# Industrial-Controller_MCU1.net
KiCad netlist of a schematic drawn in Altium Designer
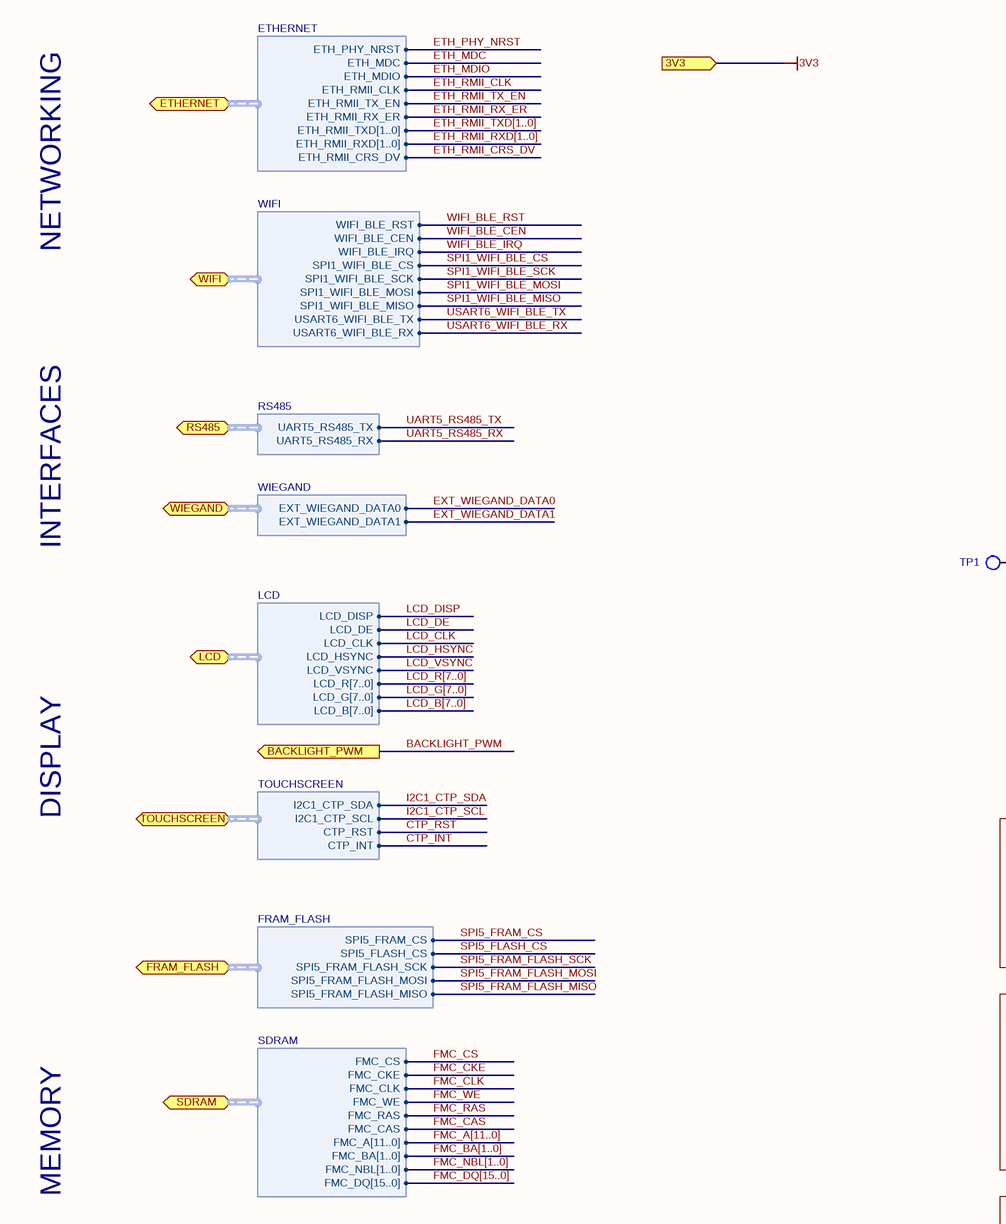
[diagram p0: Industrial-Controller_MCU1.SchDoc, top left]
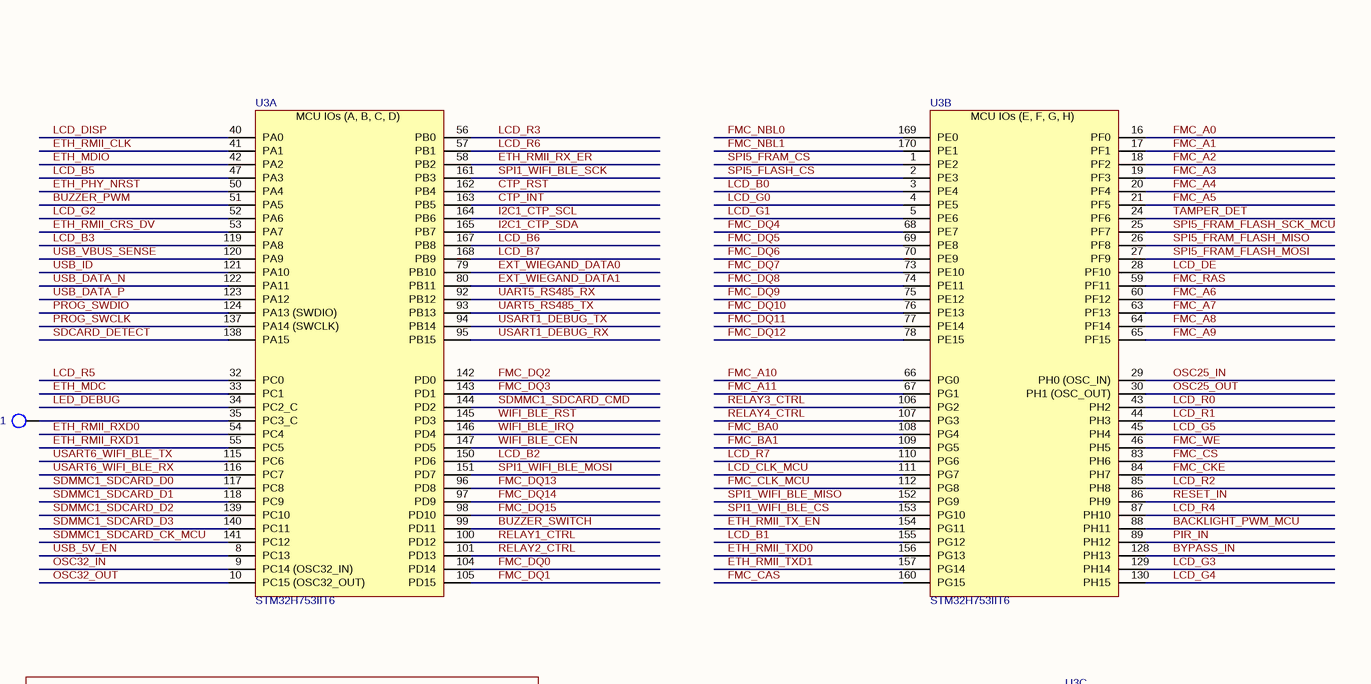
[diagram p1: Industrial-Controller_MCU1.SchDoc, top right]
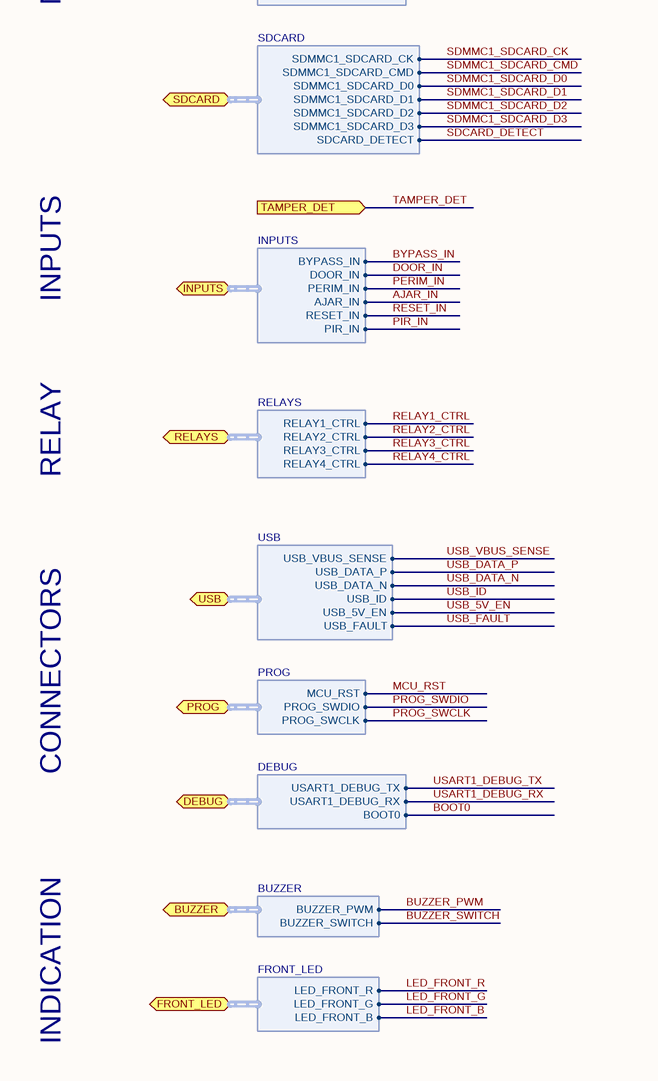
[diagram p2: Industrial-Controller_MCU1.SchDoc, bottom left]
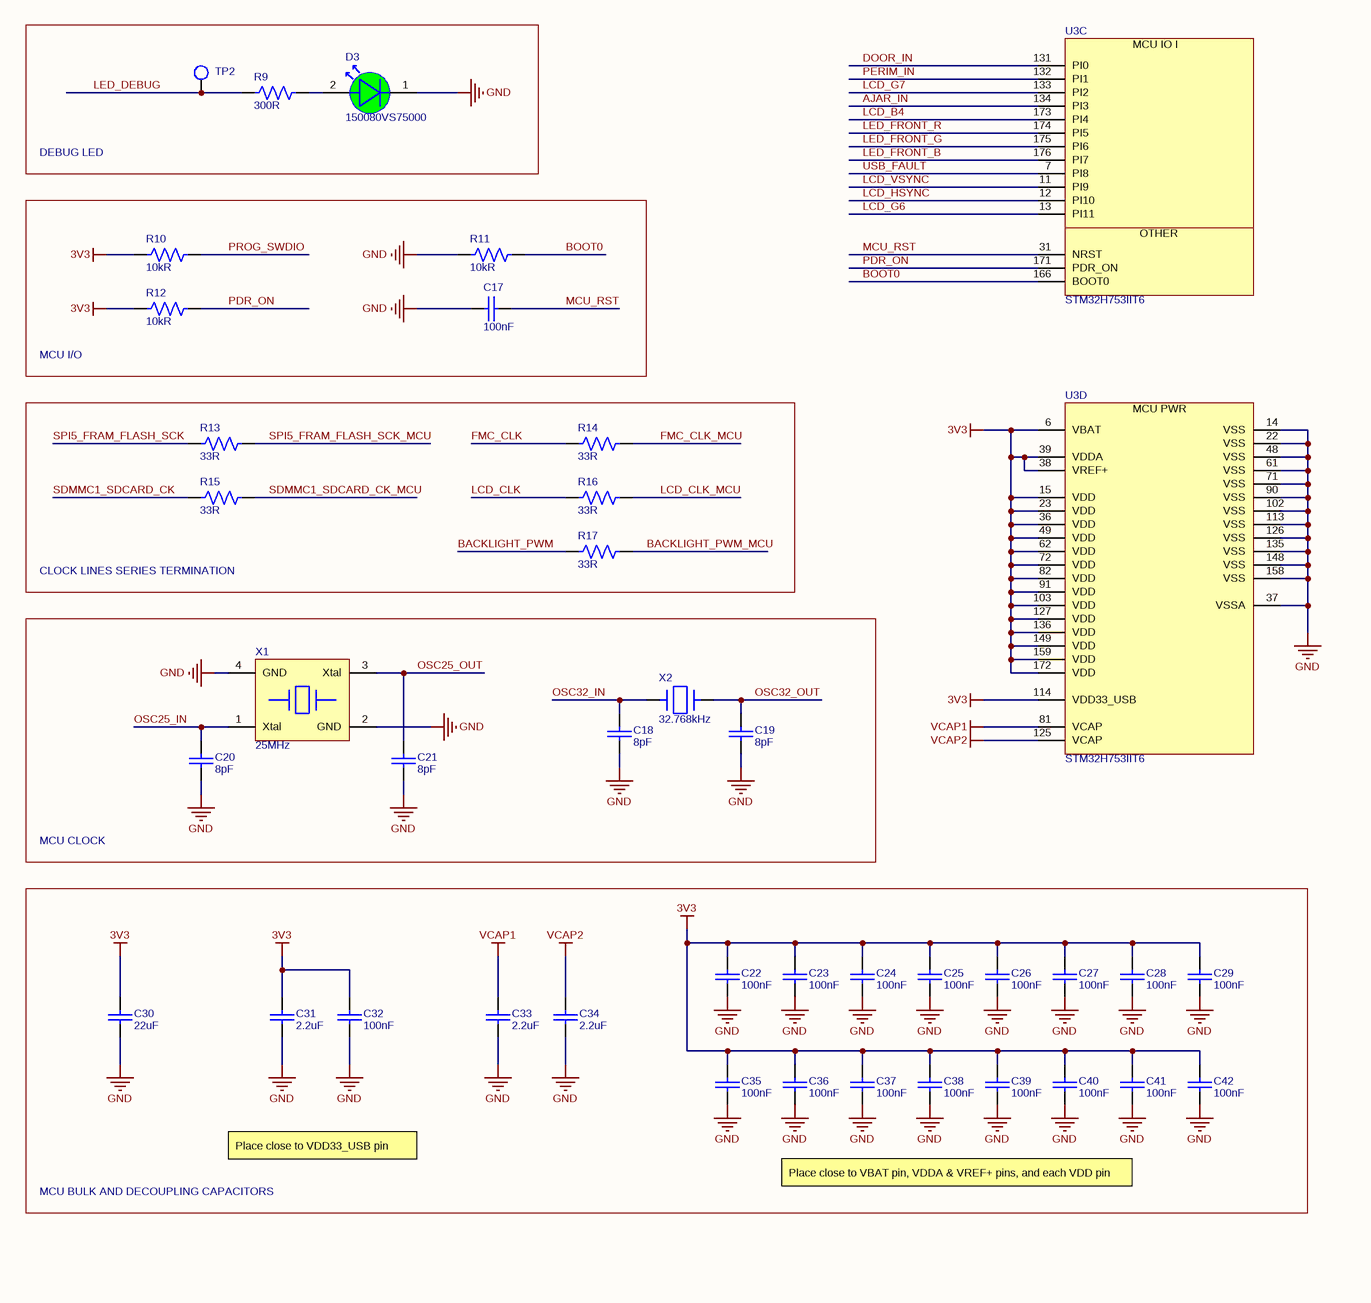
[diagram p3: Industrial-Controller_MCU1.SchDoc, bottom right]

(export (version "E")
  (design (tool "Eeschema 10.0.6"))
  (components
    (comp (ref "C17")
      (value "100nF")
      (footprint "CAP_0603")
      (description "CAP CER 0.1UF 50V X7R 0603")
      (fields (field (name "TOLERANCE") "10%"))
      (libsource (lib "Door_Controller_Single") (part "CL10B104KB8NNNL"))
    )
    (comp (ref "C18")
      (value "8pF")
      (footprint "CAP_0603")
      (description "CAP CER 8PF 50V C0G/NPO 0603")
      (libsource (lib "Door_Controller_Single") (part "CC0603DRNPO9BN8R0"))
    )
    (comp (ref "C19")
      (value "8pF")
      (footprint "CAP_0603")
      (description "CAP CER 8PF 50V C0G/NPO 0603")
      (libsource (lib "Door_Controller_Single") (part "CC0603DRNPO9BN8R0"))
    )
    (comp (ref "C20")
      (value "8pF")
      (footprint "CAP_0603")
      (description "CAP CER 8PF 50V C0G/NPO 0603")
      (libsource (lib "Door_Controller_Single") (part "CC0603DRNPO9BN8R0"))
    )
    (comp (ref "C21")
      (value "8pF")
      (footprint "CAP_0603")
      (description "CAP CER 8PF 50V C0G/NPO 0603")
      (libsource (lib "Door_Controller_Single") (part "CC0603DRNPO9BN8R0"))
    )
    (comp (ref "C22")
      (value "100nF")
      (footprint "CAP_0603")
      (description "CAP CER 0.1UF 50V X7R 0603")
      (fields (field (name "TOLERANCE") "10%"))
      (libsource (lib "Door_Controller_Single") (part "CL10B104KB8NNNL"))
    )
    (comp (ref "C23")
      (value "100nF")
      (footprint "CAP_0603")
      (description "CAP CER 0.1UF 50V X7R 0603")
      (fields (field (name "TOLERANCE") "10%"))
      (libsource (lib "Door_Controller_Single") (part "CL10B104KB8NNNL"))
    )
    (comp (ref "C24")
      (value "100nF")
      (footprint "CAP_0603")
      (description "CAP CER 0.1UF 50V X7R 0603")
      (fields (field (name "TOLERANCE") "10%"))
      (libsource (lib "Door_Controller_Single") (part "CL10B104KB8NNNL"))
    )
    (comp (ref "C25")
      (value "100nF")
      (footprint "CAP_0603")
      (description "CAP CER 0.1UF 50V X7R 0603")
      (fields (field (name "TOLERANCE") "10%"))
      (libsource (lib "Door_Controller_Single") (part "CL10B104KB8NNNL"))
    )
    (comp (ref "C26")
      (value "100nF")
      (footprint "CAP_0603")
      (description "CAP CER 0.1UF 50V X7R 0603")
      (fields (field (name "TOLERANCE") "10%"))
      (libsource (lib "Door_Controller_Single") (part "CL10B104KB8NNNL"))
    )
    (comp (ref "C27")
      (value "100nF")
      (footprint "CAP_0603")
      (description "CAP CER 0.1UF 50V X7R 0603")
      (fields (field (name "TOLERANCE") "10%"))
      (libsource (lib "Door_Controller_Single") (part "CL10B104KB8NNNL"))
    )
    (comp (ref "C28")
      (value "100nF")
      (footprint "CAP_0603")
      (description "CAP CER 0.1UF 50V X7R 0603")
      (fields (field (name "TOLERANCE") "10%"))
      (libsource (lib "Door_Controller_Single") (part "CL10B104KB8NNNL"))
    )
    (comp (ref "C29")
      (value "100nF")
      (footprint "CAP_0603")
      (description "CAP CER 0.1UF 50V X7R 0603")
      (fields (field (name "TOLERANCE") "10%"))
      (libsource (lib "Door_Controller_Single") (part "CL10B104KB8NNNL"))
    )
    (comp (ref "C30")
      (value "22uF")
      (footprint "CAP_1210")
      (description "CAP CER 22UF 25V X7R 1210")
      (fields (field (name "TOLERANCE") "10%"))
      (libsource (lib "Door_Controller_Single") (part "CL32B226KAJNNNE"))
    )
    (comp (ref "C31")
      (value "2.2uF")
      (footprint "CAP_0603")
      (description "CAP CER 2.2UF 10V X7R 0603")
      (fields (field (name "TOLERANCE") "10%"))
      (libsource (lib "Door_Controller_Single") (part "CL10B225KP8NNNC"))
    )
    (comp (ref "C32")
      (value "100nF")
      (footprint "CAP_0603")
      (description "CAP CER 0.1UF 50V X7R 0603")
      (fields (field (name "TOLERANCE") "10%"))
      (libsource (lib "Door_Controller_Single") (part "CL10B104KB8NNNL"))
    )
    (comp (ref "C33")
      (value "2.2uF")
      (footprint "CAP_0603")
      (description "CAP CER 2.2UF 10V X7R 0603")
      (fields (field (name "TOLERANCE") "10%"))
      (libsource (lib "Door_Controller_Single") (part "CL10B225KP8NNNC"))
    )
    (comp (ref "C34")
      (value "2.2uF")
      (footprint "CAP_0603")
      (description "CAP CER 2.2UF 10V X7R 0603")
      (fields (field (name "TOLERANCE") "10%"))
      (libsource (lib "Door_Controller_Single") (part "CL10B225KP8NNNC"))
    )
    (comp (ref "C35")
      (value "100nF")
      (footprint "CAP_0603")
      (description "CAP CER 0.1UF 50V X7R 0603")
      (fields (field (name "TOLERANCE") "10%"))
      (libsource (lib "Door_Controller_Single") (part "CL10B104KB8NNNL"))
    )
    (comp (ref "C36")
      (value "100nF")
      (footprint "CAP_0603")
      (description "CAP CER 0.1UF 50V X7R 0603")
      (fields (field (name "TOLERANCE") "10%"))
      (libsource (lib "Door_Controller_Single") (part "CL10B104KB8NNNL"))
    )
    (comp (ref "C37")
      (value "100nF")
      (footprint "CAP_0603")
      (description "CAP CER 0.1UF 50V X7R 0603")
      (fields (field (name "TOLERANCE") "10%"))
      (libsource (lib "Door_Controller_Single") (part "CL10B104KB8NNNL"))
    )
    (comp (ref "C38")
      (value "100nF")
      (footprint "CAP_0603")
      (description "CAP CER 0.1UF 50V X7R 0603")
      (fields (field (name "TOLERANCE") "10%"))
      (libsource (lib "Door_Controller_Single") (part "CL10B104KB8NNNL"))
    )
    (comp (ref "C39")
      (value "100nF")
      (footprint "CAP_0603")
      (description "CAP CER 0.1UF 50V X7R 0603")
      (fields (field (name "TOLERANCE") "10%"))
      (libsource (lib "Door_Controller_Single") (part "CL10B104KB8NNNL"))
    )
    (comp (ref "C40")
      (value "100nF")
      (footprint "CAP_0603")
      (description "CAP CER 0.1UF 50V X7R 0603")
      (fields (field (name "TOLERANCE") "10%"))
      (libsource (lib "Door_Controller_Single") (part "CL10B104KB8NNNL"))
    )
    (comp (ref "C41")
      (value "100nF")
      (footprint "CAP_0603")
      (description "CAP CER 0.1UF 50V X7R 0603")
      (fields (field (name "TOLERANCE") "10%"))
      (libsource (lib "Door_Controller_Single") (part "CL10B104KB8NNNL"))
    )
    (comp (ref "C42")
      (value "100nF")
      (footprint "CAP_0603")
      (description "CAP CER 0.1UF 50V X7R 0603")
      (fields (field (name "TOLERANCE") "10%"))
      (libsource (lib "Door_Controller_Single") (part "CL10B104KB8NNNL"))
    )
    (comp (ref "D3")
      (value "150080VS75000")
      (footprint "LED_0805")
      (description "LED GREEN CLEAR 0805 SMD")
      (libsource (lib "Door_Controller_Single") (part "150080VS75000"))
    )
    (comp (ref "R9")
      (value "300R")
      (footprint "RES_0603")
      (description "RES 300 OHM 5% 1/10W 0603")
      (fields (field (name "TOLERANCE") "5%"))
      (libsource (lib "Door_Controller_Single") (part "RC0603JR-07300RL"))
    )
    (comp (ref "R10")
      (value "10kR")
      (footprint "RES_0603")
      (description "RES SMD 10K OHM 5% 1/10W 0603")
      (fields (field (name "TOLERANCE") "5%"))
      (libsource (lib "Door_Controller_Single") (part "RC0603JR-0710KP"))
    )
    (comp (ref "R11")
      (value "10kR")
      (footprint "RES_0603")
      (description "RES SMD 10K OHM 5% 1/10W 0603")
      (fields (field (name "TOLERANCE") "5%"))
      (libsource (lib "Door_Controller_Single") (part "RC0603JR-0710KP"))
    )
    (comp (ref "R12")
      (value "10kR")
      (footprint "RES_0603")
      (description "RES SMD 10K OHM 5% 1/10W 0603")
      (fields (field (name "TOLERANCE") "5%"))
      (libsource (lib "Door_Controller_Single") (part "RC0603JR-0710KP"))
    )
    (comp (ref "R13")
      (value "33R")
      (footprint "RES_0603")
      (description "RES 33 OHM 5% 1/10W 0603")
      (fields (field (name "TOLERANCE") "5%"))
      (libsource (lib "Door_Controller_Single") (part "RC0603JR-0733RL"))
    )
    (comp (ref "R14")
      (value "33R")
      (footprint "RES_0603")
      (description "RES 33 OHM 5% 1/10W 0603")
      (fields (field (name "TOLERANCE") "5%"))
      (libsource (lib "Door_Controller_Single") (part "RC0603JR-0733RL"))
    )
    (comp (ref "R15")
      (value "33R")
      (footprint "RES_0603")
      (description "RES 33 OHM 5% 1/10W 0603")
      (fields (field (name "TOLERANCE") "5%"))
      (libsource (lib "Door_Controller_Single") (part "RC0603JR-0733RL"))
    )
    (comp (ref "R16")
      (value "33R")
      (footprint "RES_0603")
      (description "RES 33 OHM 5% 1/10W 0603")
      (fields (field (name "TOLERANCE") "5%"))
      (libsource (lib "Door_Controller_Single") (part "RC0603JR-0733RL"))
    )
    (comp (ref "R17")
      (value "33R")
      (footprint "RES_0603")
      (description "RES 33 OHM 5% 1/10W 0603")
      (fields (field (name "TOLERANCE") "5%"))
      (libsource (lib "Door_Controller_Single") (part "RC0603JR-0733RL"))
    )
    (comp (ref "TP1")
      (value "TEST_POINT_SMT")
      (footprint "TEST_POINT_SMT")
      (description "STM test point")
      (libsource (lib "Door_Controller_Single") (part "TEST_POINT_SMT"))
    )
    (comp (ref "TP2")
      (value "TEST_POINT_SMT")
      (footprint "TEST_POINT_SMT")
      (description "STM test point")
      (libsource (lib "Door_Controller_Single") (part "TEST_POINT_SMT"))
    )
    (comp (ref "U3")
      (value "STM32H753IIT6")
      (footprint "LQFP176")
      (description "IC MCU 32BIT 2MB FLASH 176LQFP")
      (libsource (lib "Door_Controller_Single") (part "STM32H753IIT6"))
    )
    (comp (ref "X1")
      (value "25MHz")
      (footprint "NX2016SA-25MHZ-EXS00A-CS11365")
      (description "Crystal 25.0000MHZ 6PF SMD")
      (libsource (lib "Door_Controller_Single") (part "NX2016SA-25MHZ-EXS00A-CS11365"))
    )
    (comp (ref "X2")
      (value "32.768kHz")
      (footprint "NX2012SA-32.768KHZ-EXS00A-MU00626")
      (description "Crystal 32.7680KHZ 6PF SMD")
      (libsource (lib "Door_Controller_Single") (part "NX2012SA-32.768KHZ-EXS00A-MU00626"))
    )
  )
  (nets
    (net (code "17") (name "/AJAR_IN") (class "Default")
      (node (ref "U3") (pin "134") (pinfunction "PI3_134") (pintype "passive"))
    )
    (net (code "18") (name "/BACKLIGHT_PWM") (class "Default")
      (node (ref "R17") (pin "1") (pinfunction "1_1") (pintype "passive"))
    )
    (net (code "19") (name "/BACKLIGHT_PWM_MCU") (class "Default")
      (node (ref "R17") (pin "2") (pinfunction "2_2") (pintype "passive"))
      (node (ref "U3") (pin "88") (pinfunction "PH11_88") (pintype "passive"))
    )
    (net (code "20") (name "/BOOT0") (class "Default")
      (node (ref "R11") (pin "2") (pinfunction "2_2") (pintype "passive"))
      (node (ref "U3") (pin "166") (pinfunction "BOOT0_166") (pintype "passive"))
    )
    (net (code "21") (name "/BUZZER_PWM") (class "Default")
      (node (ref "U3") (pin "51") (pinfunction "PA5_51") (pintype "passive"))
    )
    (net (code "22") (name "/BUZZER_SWITCH") (class "Default")
      (node (ref "U3") (pin "99") (pinfunction "PD11_99") (pintype "passive"))
    )
    (net (code "23") (name "/BYPASS_IN") (class "Default")
      (node (ref "U3") (pin "128") (pinfunction "PH13_128") (pintype "passive"))
    )
    (net (code "24") (name "/CTP_INT") (class "Default")
      (node (ref "U3") (pin "163") (pinfunction "PB5_163") (pintype "passive"))
    )
    (net (code "25") (name "/CTP_RST") (class "Default")
      (node (ref "U3") (pin "162") (pinfunction "PB4_162") (pintype "passive"))
    )
    (net (code "26") (name "/DOOR_IN") (class "Default")
      (node (ref "U3") (pin "131") (pinfunction "PI0_131") (pintype "passive"))
    )
    (net (code "28") (name "/ETH_MDC") (class "Default")
      (node (ref "U3") (pin "33") (pinfunction "PC1_33") (pintype "passive"))
    )
    (net (code "29") (name "/ETH_MDIO") (class "Default")
      (node (ref "U3") (pin "42") (pinfunction "PA2_42") (pintype "passive"))
    )
    (net (code "30") (name "/ETH_PHY_NRST") (class "Default")
      (node (ref "U3") (pin "50") (pinfunction "PA4_50") (pintype "passive"))
    )
    (net (code "31") (name "/ETH_RMII_CLK") (class "Default")
      (node (ref "U3") (pin "41") (pinfunction "PA1_41") (pintype "passive"))
    )
    (net (code "32") (name "/ETH_RMII_CRS_DV") (class "Default")
      (node (ref "U3") (pin "53") (pinfunction "PA7_53") (pintype "passive"))
    )
    (net (code "33") (name "/ETH_RMII_RXD0") (class "Default")
      (node (ref "U3") (pin "54") (pinfunction "PC4_54") (pintype "passive"))
    )
    (net (code "34") (name "/ETH_RMII_RXD1") (class "Default")
      (node (ref "U3") (pin "55") (pinfunction "PC5_55") (pintype "passive"))
    )
    (net (code "35") (name "/ETH_RMII_RX_ER") (class "Default")
      (node (ref "U3") (pin "58") (pinfunction "PB2_58") (pintype "passive"))
    )
    (net (code "36") (name "/ETH_RMII_TXD0") (class "Default")
      (node (ref "U3") (pin "156") (pinfunction "PG13_156") (pintype "passive"))
    )
    (net (code "37") (name "/ETH_RMII_TXD1") (class "Default")
      (node (ref "U3") (pin "157") (pinfunction "PG14_157") (pintype "passive"))
    )
    (net (code "39") (name "/ETH_RMII_TX_EN") (class "Default")
      (node (ref "U3") (pin "154") (pinfunction "PG11_154") (pintype "passive"))
    )
    (net (code "40") (name "/EXT_WIEGAND_DATA0") (class "Default")
      (node (ref "U3") (pin "79") (pinfunction "PB10_79") (pintype "passive"))
    )
    (net (code "41") (name "/EXT_WIEGAND_DATA1") (class "Default")
      (node (ref "U3") (pin "80") (pinfunction "PB11_80") (pintype "passive"))
    )
    (net (code "42") (name "/FMC_A0") (class "Default")
      (node (ref "U3") (pin "16") (pinfunction "PF0_16") (pintype "passive"))
    )
    (net (code "43") (name "/FMC_A1") (class "Default")
      (node (ref "U3") (pin "17") (pinfunction "PF1_17") (pintype "passive"))
    )
    (net (code "44") (name "/FMC_A2") (class "Default")
      (node (ref "U3") (pin "18") (pinfunction "PF2_18") (pintype "passive"))
    )
    (net (code "45") (name "/FMC_A3") (class "Default")
      (node (ref "U3") (pin "19") (pinfunction "PF3_19") (pintype "passive"))
    )
    (net (code "46") (name "/FMC_A4") (class "Default")
      (node (ref "U3") (pin "20") (pinfunction "PF4_20") (pintype "passive"))
    )
    (net (code "47") (name "/FMC_A5") (class "Default")
      (node (ref "U3") (pin "21") (pinfunction "PF5_21") (pintype "passive"))
    )
    (net (code "48") (name "/FMC_A6") (class "Default")
      (node (ref "U3") (pin "60") (pinfunction "PF12_60") (pintype "passive"))
    )
    (net (code "49") (name "/FMC_A7") (class "Default")
      (node (ref "U3") (pin "63") (pinfunction "PF13_63") (pintype "passive"))
    )
    (net (code "50") (name "/FMC_A8") (class "Default")
      (node (ref "U3") (pin "64") (pinfunction "PF14_64") (pintype "passive"))
    )
    (net (code "51") (name "/FMC_A9") (class "Default")
      (node (ref "U3") (pin "65") (pinfunction "PF15_65") (pintype "passive"))
    )
    (net (code "52") (name "/FMC_A10") (class "Default")
      (node (ref "U3") (pin "66") (pinfunction "PG0_66") (pintype "passive"))
    )
    (net (code "53") (name "/FMC_A11") (class "Default")
      (node (ref "U3") (pin "67") (pinfunction "PG1_67") (pintype "passive"))
    )
    (net (code "54") (name "/FMC_BA0") (class "Default")
      (node (ref "U3") (pin "108") (pinfunction "PG4_108") (pintype "passive"))
    )
    (net (code "55") (name "/FMC_BA1") (class "Default")
      (node (ref "U3") (pin "109") (pinfunction "PG5_109") (pintype "passive"))
    )
    (net (code "57") (name "/FMC_CAS") (class "Default")
      (node (ref "U3") (pin "160") (pinfunction "PG15_160") (pintype "passive"))
    )
    (net (code "58") (name "/FMC_CKE") (class "Default")
      (node (ref "U3") (pin "84") (pinfunction "PH7_84") (pintype "passive"))
    )
    (net (code "59") (name "/FMC_CLK") (class "Default")
      (node (ref "R14") (pin "1") (pinfunction "1_1") (pintype "passive"))
    )
    (net (code "60") (name "/FMC_CLK_MCU") (class "Default")
      (node (ref "R14") (pin "2") (pinfunction "2_2") (pintype "passive"))
      (node (ref "U3") (pin "112") (pinfunction "PG8_112") (pintype "passive"))
    )
    (net (code "61") (name "/FMC_CS") (class "Default")
      (node (ref "U3") (pin "83") (pinfunction "PH6_83") (pintype "passive"))
    )
    (net (code "62") (name "/FMC_DQ0") (class "Default")
      (node (ref "U3") (pin "104") (pinfunction "PD14_104") (pintype "passive"))
    )
    (net (code "63") (name "/FMC_DQ1") (class "Default")
      (node (ref "U3") (pin "105") (pinfunction "PD15_105") (pintype "passive"))
    )
    (net (code "64") (name "/FMC_DQ2") (class "Default")
      (node (ref "U3") (pin "142") (pinfunction "PD0_142") (pintype "passive"))
    )
    (net (code "65") (name "/FMC_DQ3") (class "Default")
      (node (ref "U3") (pin "143") (pinfunction "PD1_143") (pintype "passive"))
    )
    (net (code "66") (name "/FMC_DQ4") (class "Default")
      (node (ref "U3") (pin "68") (pinfunction "PE7_68") (pintype "passive"))
    )
    (net (code "67") (name "/FMC_DQ5") (class "Default")
      (node (ref "U3") (pin "69") (pinfunction "PE8_69") (pintype "passive"))
    )
    (net (code "68") (name "/FMC_DQ6") (class "Default")
      (node (ref "U3") (pin "70") (pinfunction "PE9_70") (pintype "passive"))
    )
    (net (code "69") (name "/FMC_DQ7") (class "Default")
      (node (ref "U3") (pin "73") (pinfunction "PE10_73") (pintype "passive"))
    )
    (net (code "70") (name "/FMC_DQ8") (class "Default")
      (node (ref "U3") (pin "74") (pinfunction "PE11_74") (pintype "passive"))
    )
    (net (code "71") (name "/FMC_DQ9") (class "Default")
      (node (ref "U3") (pin "75") (pinfunction "PE12_75") (pintype "passive"))
    )
    (net (code "72") (name "/FMC_DQ10") (class "Default")
      (node (ref "U3") (pin "76") (pinfunction "PE13_76") (pintype "passive"))
    )
    (net (code "73") (name "/FMC_DQ11") (class "Default")
      (node (ref "U3") (pin "77") (pinfunction "PE14_77") (pintype "passive"))
    )
    (net (code "74") (name "/FMC_DQ12") (class "Default")
      (node (ref "U3") (pin "78") (pinfunction "PE15_78") (pintype "passive"))
    )
    (net (code "75") (name "/FMC_DQ13") (class "Default")
      (node (ref "U3") (pin "96") (pinfunction "PD8_96") (pintype "passive"))
    )
    (net (code "76") (name "/FMC_DQ14") (class "Default")
      (node (ref "U3") (pin "97") (pinfunction "PD9_97") (pintype "passive"))
    )
    (net (code "77") (name "/FMC_DQ15") (class "Default")
      (node (ref "U3") (pin "98") (pinfunction "PD10_98") (pintype "passive"))
    )
    (net (code "79") (name "/FMC_NBL0") (class "Default")
      (node (ref "U3") (pin "169") (pinfunction "PE0_169") (pintype "passive"))
    )
    (net (code "80") (name "/FMC_NBL1") (class "Default")
      (node (ref "U3") (pin "170") (pinfunction "PE1_170") (pintype "passive"))
    )
    (net (code "82") (name "/FMC_RAS") (class "Default")
      (node (ref "U3") (pin "59") (pinfunction "PF11_59") (pintype "passive"))
    )
    (net (code "83") (name "/FMC_WE") (class "Default")
      (node (ref "U3") (pin "46") (pinfunction "PH5_46") (pintype "passive"))
    )
    (net (code "84") (name "/I2C1_CTP_SCL") (class "Default")
      (node (ref "U3") (pin "164") (pinfunction "PB6_164") (pintype "passive"))
    )
    (net (code "85") (name "/I2C1_CTP_SDA") (class "Default")
      (node (ref "U3") (pin "165") (pinfunction "PB7_165") (pintype "passive"))
    )
    (net (code "86") (name "/LCD_B0") (class "Default")
      (node (ref "U3") (pin "3") (pinfunction "PE4_3") (pintype "passive"))
    )
    (net (code "87") (name "/LCD_B1") (class "Default")
      (node (ref "U3") (pin "155") (pinfunction "PG12_155") (pintype "passive"))
    )
    (net (code "88") (name "/LCD_B2") (class "Default")
      (node (ref "U3") (pin "150") (pinfunction "PD6_150") (pintype "passive"))
    )
    (net (code "89") (name "/LCD_B3") (class "Default")
      (node (ref "U3") (pin "119") (pinfunction "PA8_119") (pintype "passive"))
    )
    (net (code "90") (name "/LCD_B4") (class "Default")
      (node (ref "U3") (pin "173") (pinfunction "PI4_173") (pintype "passive"))
    )
    (net (code "91") (name "/LCD_B5") (class "Default")
      (node (ref "U3") (pin "47") (pinfunction "PA3_47") (pintype "passive"))
    )
    (net (code "92") (name "/LCD_B6") (class "Default")
      (node (ref "U3") (pin "167") (pinfunction "PB8_167") (pintype "passive"))
    )
    (net (code "93") (name "/LCD_B7") (class "Default")
      (node (ref "U3") (pin "168") (pinfunction "PB9_168") (pintype "passive"))
    )
    (net (code "94") (name "/LCD_CLK") (class "Default")
      (node (ref "R16") (pin "1") (pinfunction "1_1") (pintype "passive"))
    )
    (net (code "95") (name "/LCD_CLK_MCU") (class "Default")
      (node (ref "R16") (pin "2") (pinfunction "2_2") (pintype "passive"))
      (node (ref "U3") (pin "111") (pinfunction "PG7_111") (pintype "passive"))
    )
    (net (code "96") (name "/LCD_DE") (class "Default")
      (node (ref "U3") (pin "28") (pinfunction "PF10_28") (pintype "passive"))
    )
    (net (code "97") (name "/LCD_DISP") (class "Default")
      (node (ref "U3") (pin "40") (pinfunction "PA0_40") (pintype "passive"))
    )
    (net (code "98") (name "/LCD_G0") (class "Default")
      (node (ref "U3") (pin "4") (pinfunction "PE5_4") (pintype "passive"))
    )
    (net (code "99") (name "/LCD_G1") (class "Default")
      (node (ref "U3") (pin "5") (pinfunction "PE6_5") (pintype "passive"))
    )
    (net (code "100") (name "/LCD_G2") (class "Default")
      (node (ref "U3") (pin "52") (pinfunction "PA6_52") (pintype "passive"))
    )
    (net (code "101") (name "/LCD_G3") (class "Default")
      (node (ref "U3") (pin "129") (pinfunction "PH14_129") (pintype "passive"))
    )
    (net (code "102") (name "/LCD_G4") (class "Default")
      (node (ref "U3") (pin "130") (pinfunction "PH15_130") (pintype "passive"))
    )
    (net (code "103") (name "/LCD_G5") (class "Default")
      (node (ref "U3") (pin "45") (pinfunction "PH4_45") (pintype "passive"))
    )
    (net (code "104") (name "/LCD_G6") (class "Default")
      (node (ref "U3") (pin "13") (pinfunction "PI11_13") (pintype "passive"))
    )
    (net (code "105") (name "/LCD_G7") (class "Default")
      (node (ref "U3") (pin "133") (pinfunction "PI2_133") (pintype "passive"))
    )
    (net (code "107") (name "/LCD_HSYNC") (class "Default")
      (node (ref "U3") (pin "12") (pinfunction "PI10_12") (pintype "passive"))
    )
    (net (code "108") (name "/LCD_R0") (class "Default")
      (node (ref "U3") (pin "43") (pinfunction "PH2_43") (pintype "passive"))
    )
    (net (code "109") (name "/LCD_R1") (class "Default")
      (node (ref "U3") (pin "44") (pinfunction "PH3_44") (pintype "passive"))
    )
    (net (code "110") (name "/LCD_R2") (class "Default")
      (node (ref "U3") (pin "85") (pinfunction "PH8_85") (pintype "passive"))
    )
    (net (code "111") (name "/LCD_R3") (class "Default")
      (node (ref "U3") (pin "56") (pinfunction "PB0_56") (pintype "passive"))
    )
    (net (code "112") (name "/LCD_R4") (class "Default")
      (node (ref "U3") (pin "87") (pinfunction "PH10_87") (pintype "passive"))
    )
    (net (code "113") (name "/LCD_R5") (class "Default")
      (node (ref "U3") (pin "32") (pinfunction "PC0_32") (pintype "passive"))
    )
    (net (code "114") (name "/LCD_R6") (class "Default")
      (node (ref "U3") (pin "57") (pinfunction "PB1_57") (pintype "passive"))
    )
    (net (code "115") (name "/LCD_R7") (class "Default")
      (node (ref "U3") (pin "110") (pinfunction "PG6_110") (pintype "passive"))
    )
    (net (code "117") (name "/LCD_VSYNC") (class "Default")
      (node (ref "U3") (pin "11") (pinfunction "PI9_11") (pintype "passive"))
    )
    (net (code "119") (name "/LED_DEBUG") (class "Default")
      (node (ref "R9") (pin "1") (pinfunction "1_1") (pintype "passive"))
      (node (ref "TP2") (pin "1") (pinfunction "1_1") (pintype "passive"))
      (node (ref "U3") (pin "34") (pinfunction "PC2_C_34") (pintype "passive"))
    )
    (net (code "120") (name "/LED_FRONT_B") (class "Default")
      (node (ref "U3") (pin "176") (pinfunction "PI7_176") (pintype "passive"))
    )
    (net (code "121") (name "/LED_FRONT_G") (class "Default")
      (node (ref "U3") (pin "175") (pinfunction "PI6_175") (pintype "passive"))
    )
    (net (code "122") (name "/LED_FRONT_R") (class "Default")
      (node (ref "U3") (pin "174") (pinfunction "PI5_174") (pintype "passive"))
    )
    (net (code "123") (name "/MCU_RST") (class "Default")
      (node (ref "C17") (pin "2") (pinfunction "2_2") (pintype "passive"))
      (node (ref "U3") (pin "31") (pinfunction "NRST_31") (pintype "passive"))
    )
    (net (code "124") (name "/OSC25_IN") (class "Default")
      (node (ref "C20") (pin "2") (pinfunction "2_2") (pintype "passive"))
      (node (ref "U3") (pin "29") (pinfunction "PH0_(OSC_IN)_29") (pintype "passive"))
      (node (ref "X1") (pin "1") (pinfunction "Xtal_1") (pintype "passive"))
    )
    (net (code "125") (name "/OSC25_OUT") (class "Default")
      (node (ref "C21") (pin "2") (pinfunction "2_2") (pintype "passive"))
      (node (ref "U3") (pin "30") (pinfunction "PH1_(OSC_OUT)_30") (pintype "passive"))
      (node (ref "X1") (pin "3") (pinfunction "Xtal_3") (pintype "passive"))
    )
    (net (code "126") (name "/OSC32_IN") (class "Default")
      (node (ref "C18") (pin "2") (pinfunction "2_2") (pintype "passive"))
      (node (ref "U3") (pin "9") (pinfunction "PC14_(OSC32_IN)_9") (pintype "passive"))
      (node (ref "X2") (pin "1") (pinfunction "1_1") (pintype "passive"))
    )
    (net (code "127") (name "/OSC32_OUT") (class "Default")
      (node (ref "C19") (pin "2") (pinfunction "2_2") (pintype "passive"))
      (node (ref "U3") (pin "10") (pinfunction "PC15_(OSC32_OUT)_10") (pintype "passive"))
      (node (ref "X2") (pin "2") (pinfunction "2_2") (pintype "passive"))
    )
    (net (code "128") (name "/PDR_ON") (class "Default")
      (node (ref "R12") (pin "2") (pinfunction "2_2") (pintype "passive"))
      (node (ref "U3") (pin "171") (pinfunction "PDR_ON_171") (pintype "passive"))
    )
    (net (code "129") (name "/PERIM_IN") (class "Default")
      (node (ref "U3") (pin "132") (pinfunction "PI1_132") (pintype "passive"))
    )
    (net (code "130") (name "/PIR_IN") (class "Default")
      (node (ref "U3") (pin "89") (pinfunction "PH12_89") (pintype "passive"))
    )
    (net (code "131") (name "/PROG_SWCLK") (class "Default")
      (node (ref "U3") (pin "137") (pinfunction "PA14_(SWCLK)_137") (pintype "passive"))
    )
    (net (code "132") (name "/PROG_SWDIO") (class "Default")
      (node (ref "R10") (pin "2") (pinfunction "2_2") (pintype "passive"))
      (node (ref "U3") (pin "124") (pinfunction "PA13_(SWDIO)_124") (pintype "passive"))
    )
    (net (code "133") (name "/RELAY1_CTRL") (class "Default")
      (node (ref "U3") (pin "100") (pinfunction "PD12_100") (pintype "passive"))
    )
    (net (code "134") (name "/RELAY2_CTRL") (class "Default")
      (node (ref "U3") (pin "101") (pinfunction "PD13_101") (pintype "passive"))
    )
    (net (code "135") (name "/RELAY3_CTRL") (class "Default")
      (node (ref "U3") (pin "106") (pinfunction "PG2_106") (pintype "passive"))
    )
    (net (code "136") (name "/RELAY4_CTRL") (class "Default")
      (node (ref "U3") (pin "107") (pinfunction "PG3_107") (pintype "passive"))
    )
    (net (code "137") (name "/RESET_IN") (class "Default")
      (node (ref "U3") (pin "86") (pinfunction "PH9_86") (pintype "passive"))
    )
    (net (code "138") (name "/SDCARD_DETECT") (class "Default")
      (node (ref "U3") (pin "138") (pinfunction "PA15_138") (pintype "passive"))
    )
    (net (code "139") (name "/SDMMC1_SDCARD_CK") (class "Default")
      (node (ref "R15") (pin "1") (pinfunction "1_1") (pintype "passive"))
    )
    (net (code "140") (name "/SDMMC1_SDCARD_CK_MCU") (class "Default")
      (node (ref "R15") (pin "2") (pinfunction "2_2") (pintype "passive"))
      (node (ref "U3") (pin "141") (pinfunction "PC12_141") (pintype "passive"))
    )
    (net (code "141") (name "/SDMMC1_SDCARD_CMD") (class "Default")
      (node (ref "U3") (pin "144") (pinfunction "PD2_144") (pintype "passive"))
    )
    (net (code "142") (name "/SDMMC1_SDCARD_D0") (class "Default")
      (node (ref "U3") (pin "117") (pinfunction "PC8_117") (pintype "passive"))
    )
    (net (code "143") (name "/SDMMC1_SDCARD_D1") (class "Default")
      (node (ref "U3") (pin "118") (pinfunction "PC9_118") (pintype "passive"))
    )
    (net (code "144") (name "/SDMMC1_SDCARD_D2") (class "Default")
      (node (ref "U3") (pin "139") (pinfunction "PC10_139") (pintype "passive"))
    )
    (net (code "145") (name "/SDMMC1_SDCARD_D3") (class "Default")
      (node (ref "U3") (pin "140") (pinfunction "PC11_140") (pintype "passive"))
    )
    (net (code "147") (name "/SPI1_WIFI_BLE_CS") (class "Default")
      (node (ref "U3") (pin "153") (pinfunction "PG10_153") (pintype "passive"))
    )
    (net (code "148") (name "/SPI1_WIFI_BLE_MISO") (class "Default")
      (node (ref "U3") (pin "152") (pinfunction "PG9_152") (pintype "passive"))
    )
    (net (code "149") (name "/SPI1_WIFI_BLE_MOSI") (class "Default")
      (node (ref "U3") (pin "151") (pinfunction "PD7_151") (pintype "passive"))
    )
    (net (code "150") (name "/SPI1_WIFI_BLE_SCK") (class "Default")
      (node (ref "U3") (pin "161") (pinfunction "PB3_161") (pintype "passive"))
    )
    (net (code "151") (name "/SPI5_FLASH_CS") (class "Default")
      (node (ref "U3") (pin "2") (pinfunction "PE3_2") (pintype "passive"))
    )
    (net (code "152") (name "/SPI5_FRAM_CS") (class "Default")
      (node (ref "U3") (pin "1") (pinfunction "PE2_1") (pintype "passive"))
    )
    (net (code "153") (name "/SPI5_FRAM_FLASH_MISO") (class "Default")
      (node (ref "U3") (pin "26") (pinfunction "PF8_26") (pintype "passive"))
    )
    (net (code "154") (name "/SPI5_FRAM_FLASH_MOSI") (class "Default")
      (node (ref "U3") (pin "27") (pinfunction "PF9_27") (pintype "passive"))
    )
    (net (code "155") (name "/SPI5_FRAM_FLASH_SCK") (class "Default")
      (node (ref "R13") (pin "1") (pinfunction "1_1") (pintype "passive"))
    )
    (net (code "156") (name "/SPI5_FRAM_FLASH_SCK_MCU") (class "Default")
      (node (ref "R13") (pin "2") (pinfunction "2_2") (pintype "passive"))
      (node (ref "U3") (pin "25") (pinfunction "PF7_25") (pintype "passive"))
    )
    (net (code "157") (name "/TAMPER_DET") (class "Default")
      (node (ref "U3") (pin "24") (pinfunction "PF6_24") (pintype "passive"))
    )
    (net (code "158") (name "/UART5_RS485_RX") (class "Default")
      (node (ref "U3") (pin "92") (pinfunction "PB12_92") (pintype "passive"))
    )
    (net (code "159") (name "/UART5_RS485_TX") (class "Default")
      (node (ref "U3") (pin "93") (pinfunction "PB13_93") (pintype "passive"))
    )
    (net (code "160") (name "/USART1_DEBUG_RX") (class "Default")
      (node (ref "U3") (pin "95") (pinfunction "PB15_95") (pintype "passive"))
    )
    (net (code "161") (name "/USART1_DEBUG_TX") (class "Default")
      (node (ref "U3") (pin "94") (pinfunction "PB14_94") (pintype "passive"))
    )
    (net (code "162") (name "/USART6_WIFI_BLE_RX") (class "Default")
      (node (ref "U3") (pin "116") (pinfunction "PC7_116") (pintype "passive"))
    )
    (net (code "163") (name "/USART6_WIFI_BLE_TX") (class "Default")
      (node (ref "U3") (pin "115") (pinfunction "PC6_115") (pintype "passive"))
    )
    (net (code "164") (name "/USB_5V_EN") (class "Default")
      (node (ref "U3") (pin "8") (pinfunction "PC13_8") (pintype "passive"))
    )
    (net (code "165") (name "/USB_DATA_N") (class "Default")
      (node (ref "U3") (pin "122") (pinfunction "PA11_122") (pintype "passive"))
    )
    (net (code "166") (name "/USB_DATA_P") (class "Default")
      (node (ref "U3") (pin "123") (pinfunction "PA12_123") (pintype "passive"))
    )
    (net (code "167") (name "/USB_FAULT") (class "Default")
      (node (ref "U3") (pin "7") (pinfunction "PI8_7") (pintype "passive"))
    )
    (net (code "168") (name "/USB_ID") (class "Default")
      (node (ref "U3") (pin "121") (pinfunction "PA10_121") (pintype "passive"))
    )
    (net (code "169") (name "/USB_VBUS_SENSE") (class "Default")
      (node (ref "U3") (pin "120") (pinfunction "PA9_120") (pintype "passive"))
    )
    (net (code "170") (name "/WIFI_BLE_CEN") (class "Default")
      (node (ref "U3") (pin "147") (pinfunction "PD5_147") (pintype "passive"))
    )
    (net (code "171") (name "/WIFI_BLE_IRQ") (class "Default")
      (node (ref "U3") (pin "146") (pinfunction "PD4_146") (pintype "passive"))
    )
    (net (code "172") (name "/WIFI_BLE_RST") (class "Default")
      (node (ref "U3") (pin "145") (pinfunction "PD3_145") (pintype "passive"))
    )
    (net (code "187") (name "3V3") (class "Default")
      (node (ref "C22") (pin "2") (pinfunction "2_2") (pintype "passive"))
      (node (ref "C23") (pin "2") (pinfunction "2_2") (pintype "passive"))
      (node (ref "C24") (pin "2") (pinfunction "2_2") (pintype "passive"))
      (node (ref "C25") (pin "2") (pinfunction "2_2") (pintype "passive"))
      (node (ref "C26") (pin "2") (pinfunction "2_2") (pintype "passive"))
      (node (ref "C27") (pin "2") (pinfunction "2_2") (pintype "passive"))
      (node (ref "C28") (pin "2") (pinfunction "2_2") (pintype "passive"))
      (node (ref "C29") (pin "2") (pinfunction "2_2") (pintype "passive"))
      (node (ref "C30") (pin "2") (pinfunction "2_2") (pintype "passive"))
      (node (ref "C31") (pin "2") (pinfunction "2_2") (pintype "passive"))
      (node (ref "C32") (pin "2") (pinfunction "2_2") (pintype "passive"))
      (node (ref "C35") (pin "2") (pinfunction "2_2") (pintype "passive"))
      (node (ref "C36") (pin "2") (pinfunction "2_2") (pintype "passive"))
      (node (ref "C37") (pin "2") (pinfunction "2_2") (pintype "passive"))
      (node (ref "C38") (pin "2") (pinfunction "2_2") (pintype "passive"))
      (node (ref "C39") (pin "2") (pinfunction "2_2") (pintype "passive"))
      (node (ref "C40") (pin "2") (pinfunction "2_2") (pintype "passive"))
      (node (ref "C41") (pin "2") (pinfunction "2_2") (pintype "passive"))
      (node (ref "C42") (pin "2") (pinfunction "2_2") (pintype "passive"))
      (node (ref "R10") (pin "1") (pinfunction "1_1") (pintype "passive"))
      (node (ref "R12") (pin "1") (pinfunction "1_1") (pintype "passive"))
      (node (ref "U3") (pin "103") (pinfunction "VDD_103") (pintype "passive"))
      (node (ref "U3") (pin "114") (pinfunction "VDD33_USB_114") (pintype "passive"))
      (node (ref "U3") (pin "127") (pinfunction "VDD_127") (pintype "passive"))
      (node (ref "U3") (pin "136") (pinfunction "VDD_136") (pintype "passive"))
      (node (ref "U3") (pin "149") (pinfunction "VDD_149") (pintype "passive"))
      (node (ref "U3") (pin "15") (pinfunction "VDD_15") (pintype "passive"))
      (node (ref "U3") (pin "159") (pinfunction "VDD_159") (pintype "passive"))
      (node (ref "U3") (pin "172") (pinfunction "VDD_172") (pintype "passive"))
      (node (ref "U3") (pin "23") (pinfunction "VDD_23") (pintype "passive"))
      (node (ref "U3") (pin "36") (pinfunction "VDD_36") (pintype "passive"))
      (node (ref "U3") (pin "38") (pinfunction "VREF+_38") (pintype "passive"))
      (node (ref "U3") (pin "39") (pinfunction "VDDA_39") (pintype "passive"))
      (node (ref "U3") (pin "49") (pinfunction "VDD_49") (pintype "passive"))
      (node (ref "U3") (pin "6") (pinfunction "VBAT_6") (pintype "passive"))
      (node (ref "U3") (pin "62") (pinfunction "VDD_62") (pintype "passive"))
      (node (ref "U3") (pin "72") (pinfunction "VDD_72") (pintype "passive"))
      (node (ref "U3") (pin "82") (pinfunction "VDD_82") (pintype "passive"))
      (node (ref "U3") (pin "91") (pinfunction "VDD_91") (pintype "passive"))
    )
    (net (code "188") (name "GND") (class "Default")
      (node (ref "C17") (pin "1") (pinfunction "1_1") (pintype "passive"))
      (node (ref "C18") (pin "1") (pinfunction "1_1") (pintype "passive"))
      (node (ref "C19") (pin "1") (pinfunction "1_1") (pintype "passive"))
      (node (ref "C20") (pin "1") (pinfunction "1_1") (pintype "passive"))
      (node (ref "C21") (pin "1") (pinfunction "1_1") (pintype "passive"))
      (node (ref "C22") (pin "1") (pinfunction "1_1") (pintype "passive"))
      (node (ref "C23") (pin "1") (pinfunction "1_1") (pintype "passive"))
      (node (ref "C24") (pin "1") (pinfunction "1_1") (pintype "passive"))
      (node (ref "C25") (pin "1") (pinfunction "1_1") (pintype "passive"))
      (node (ref "C26") (pin "1") (pinfunction "1_1") (pintype "passive"))
      (node (ref "C27") (pin "1") (pinfunction "1_1") (pintype "passive"))
      (node (ref "C28") (pin "1") (pinfunction "1_1") (pintype "passive"))
      (node (ref "C29") (pin "1") (pinfunction "1_1") (pintype "passive"))
      (node (ref "C30") (pin "1") (pinfunction "1_1") (pintype "passive"))
      (node (ref "C31") (pin "1") (pinfunction "1_1") (pintype "passive"))
      (node (ref "C32") (pin "1") (pinfunction "1_1") (pintype "passive"))
      (node (ref "C33") (pin "1") (pinfunction "1_1") (pintype "passive"))
      (node (ref "C34") (pin "1") (pinfunction "1_1") (pintype "passive"))
      (node (ref "C35") (pin "1") (pinfunction "1_1") (pintype "passive"))
      (node (ref "C36") (pin "1") (pinfunction "1_1") (pintype "passive"))
      (node (ref "C37") (pin "1") (pinfunction "1_1") (pintype "passive"))
      (node (ref "C38") (pin "1") (pinfunction "1_1") (pintype "passive"))
      (node (ref "C39") (pin "1") (pinfunction "1_1") (pintype "passive"))
      (node (ref "C40") (pin "1") (pinfunction "1_1") (pintype "passive"))
      (node (ref "C41") (pin "1") (pinfunction "1_1") (pintype "passive"))
      (node (ref "C42") (pin "1") (pinfunction "1_1") (pintype "passive"))
      (node (ref "D3") (pin "1") (pinfunction "C_1") (pintype "passive"))
      (node (ref "R11") (pin "1") (pinfunction "1_1") (pintype "passive"))
      (node (ref "U3") (pin "102") (pinfunction "VSS_102") (pintype "passive"))
      (node (ref "U3") (pin "113") (pinfunction "VSS_113") (pintype "passive"))
      (node (ref "U3") (pin "126") (pinfunction "VSS_126") (pintype "passive"))
      (node (ref "U3") (pin "135") (pinfunction "VSS_135") (pintype "passive"))
      (node (ref "U3") (pin "14") (pinfunction "VSS_14") (pintype "passive"))
      (node (ref "U3") (pin "148") (pinfunction "VSS_148") (pintype "passive"))
      (node (ref "U3") (pin "158") (pinfunction "VSS_158") (pintype "passive"))
      (node (ref "U3") (pin "22") (pinfunction "VSS_22") (pintype "passive"))
      (node (ref "U3") (pin "37") (pinfunction "VSSA_37") (pintype "passive"))
      (node (ref "U3") (pin "48") (pinfunction "VSS_48") (pintype "passive"))
      (node (ref "U3") (pin "61") (pinfunction "VSS_61") (pintype "passive"))
      (node (ref "U3") (pin "71") (pinfunction "VSS_71") (pintype "passive"))
      (node (ref "U3") (pin "90") (pinfunction "VSS_90") (pintype "passive"))
      (node (ref "X1") (pin "2") (pinfunction "GND_2") (pintype "passive"))
      (node (ref "X1") (pin "4") (pinfunction "GND_4") (pintype "passive"))
    )
    (net (code "189") (name "Net-(D3-A)") (class "Default")
      (node (ref "D3") (pin "2") (pinfunction "A_2") (pintype "passive"))
      (node (ref "R9") (pin "2") (pinfunction "2_2") (pintype "passive"))
    )
    (net (code "190") (name "Net-(U3A-PC3_C)") (class "Default")
      (node (ref "TP1") (pin "1") (pinfunction "1_1") (pintype "passive"))
      (node (ref "U3") (pin "35") (pinfunction "PC3_C_35") (pintype "passive"))
    )
    (net (code "191") (name "VCAP1") (class "Default")
      (node (ref "C33") (pin "2") (pinfunction "2_2") (pintype "passive"))
      (node (ref "U3") (pin "81") (pinfunction "VCAP_81") (pintype "passive"))
    )
    (net (code "192") (name "VCAP2") (class "Default")
      (node (ref "C34") (pin "2") (pinfunction "2_2") (pintype "passive"))
      (node (ref "U3") (pin "125") (pinfunction "VCAP_125") (pintype "passive"))
    )
  )
)
